# Parent_Sheet.net
KiCad netlist of a schematic drawn in Altium Designer
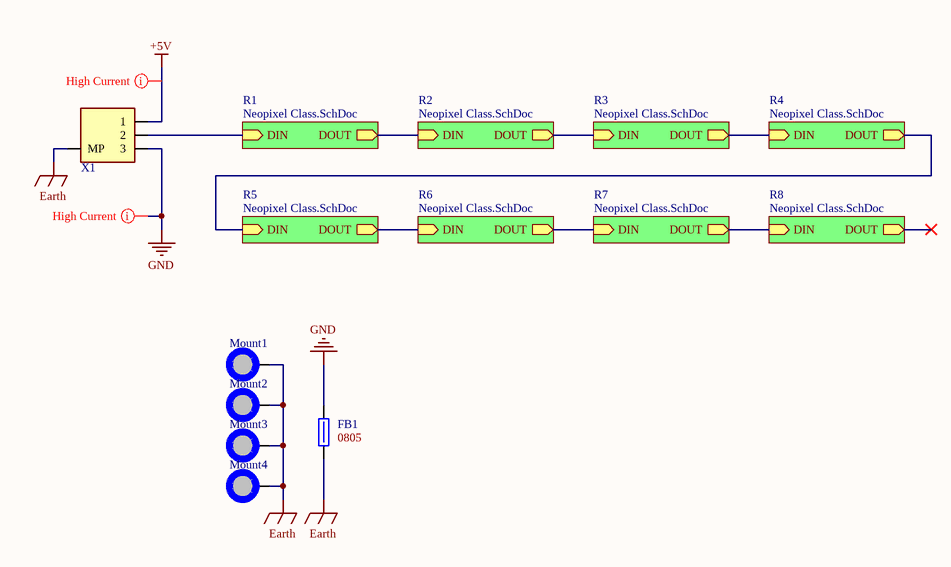
[diagram p0: Parent Sheet.SchDoc]

(export (version "E")
  (design (tool "Eeschema 10.0.6"))
  (components
    (comp (ref "FB1")
      (value "652-MH2029-300Y")
      (footprint "[Ferrite] SMD 0805")
      (fields (field (name "SIZE PACKAGE") "0805"))
      (libsource (lib "Ferrite Beads") (part "[Ferrite] SMD 0805 3A 30ohm"))
    )
    (comp (ref "Mount1")
      (value "M3 Mount Hole")
      (footprint "[Mount] M3 Mount Hole")
      (description "Place at least 4.5mm from board edge. Plated.")
      (libsource (lib "Mounts, Pads, Vias") (part "[Mount] M3 Mount Hole"))
    )
    (comp (ref "Mount2")
      (value "M3 Mount Hole")
      (footprint "[Mount] M3 Mount Hole")
      (description "Place at least 4.5mm from board edge. Plated.")
      (libsource (lib "Mounts, Pads, Vias") (part "[Mount] M3 Mount Hole"))
    )
    (comp (ref "Mount3")
      (value "M3 Mount Hole")
      (footprint "[Mount] M3 Mount Hole")
      (description "Place at least 4.5mm from board edge. Plated.")
      (libsource (lib "Mounts, Pads, Vias") (part "[Mount] M3 Mount Hole"))
    )
    (comp (ref "Mount4")
      (value "M3 Mount Hole")
      (footprint "[Mount] M3 Mount Hole")
      (description "Place at least 4.5mm from board edge. Plated.")
      (libsource (lib "Mounts, Pads, Vias") (part "[Mount] M3 Mount Hole"))
    )
    (comp (ref "X1")
      (value "[Pheonix] 3pin 2.5mm pitch")
      (footprint "[Pheonix] 3pin 2.5mm pitch")
      (description "1778777")
      (libsource (lib "Connectors") (part "[Pheonix] 3pin 2.5mm pitch"))
    )
  )
  (nets
    (net (code "1") (name "+5V") (class "Default")
      (node (ref "X1") (pin "1") (pinfunction "1_1") (pintype "passive"))
    )
    (net (code "2") (name "/DIN") (class "Default")
      (node (ref "X1") (pin "2") (pinfunction "2_2") (pintype "passive"))
    )
    (net (code "11") (name "Earth") (class "Default")
      (node (ref "FB1") (pin "1") (pinfunction "1_1") (pintype "passive"))
      (node (ref "Mount1") (pin "1") (pintype "power_in"))
      (node (ref "Mount2") (pin "1") (pintype "power_in"))
      (node (ref "Mount3") (pin "1") (pintype "power_in"))
      (node (ref "Mount4") (pin "1") (pintype "power_in"))
      (node (ref "X1") (pin "MP") (pinfunction "MP_MP") (pintype "passive"))
    )
    (net (code "12") (name "GND") (class "Default")
      (node (ref "FB1") (pin "2") (pinfunction "2_2") (pintype "passive"))
      (node (ref "X1") (pin "3") (pinfunction "3_3") (pintype "passive"))
    )
  )
)
